# branches_v40.net
KiCad netlist of a schematic drawn in EAGLE
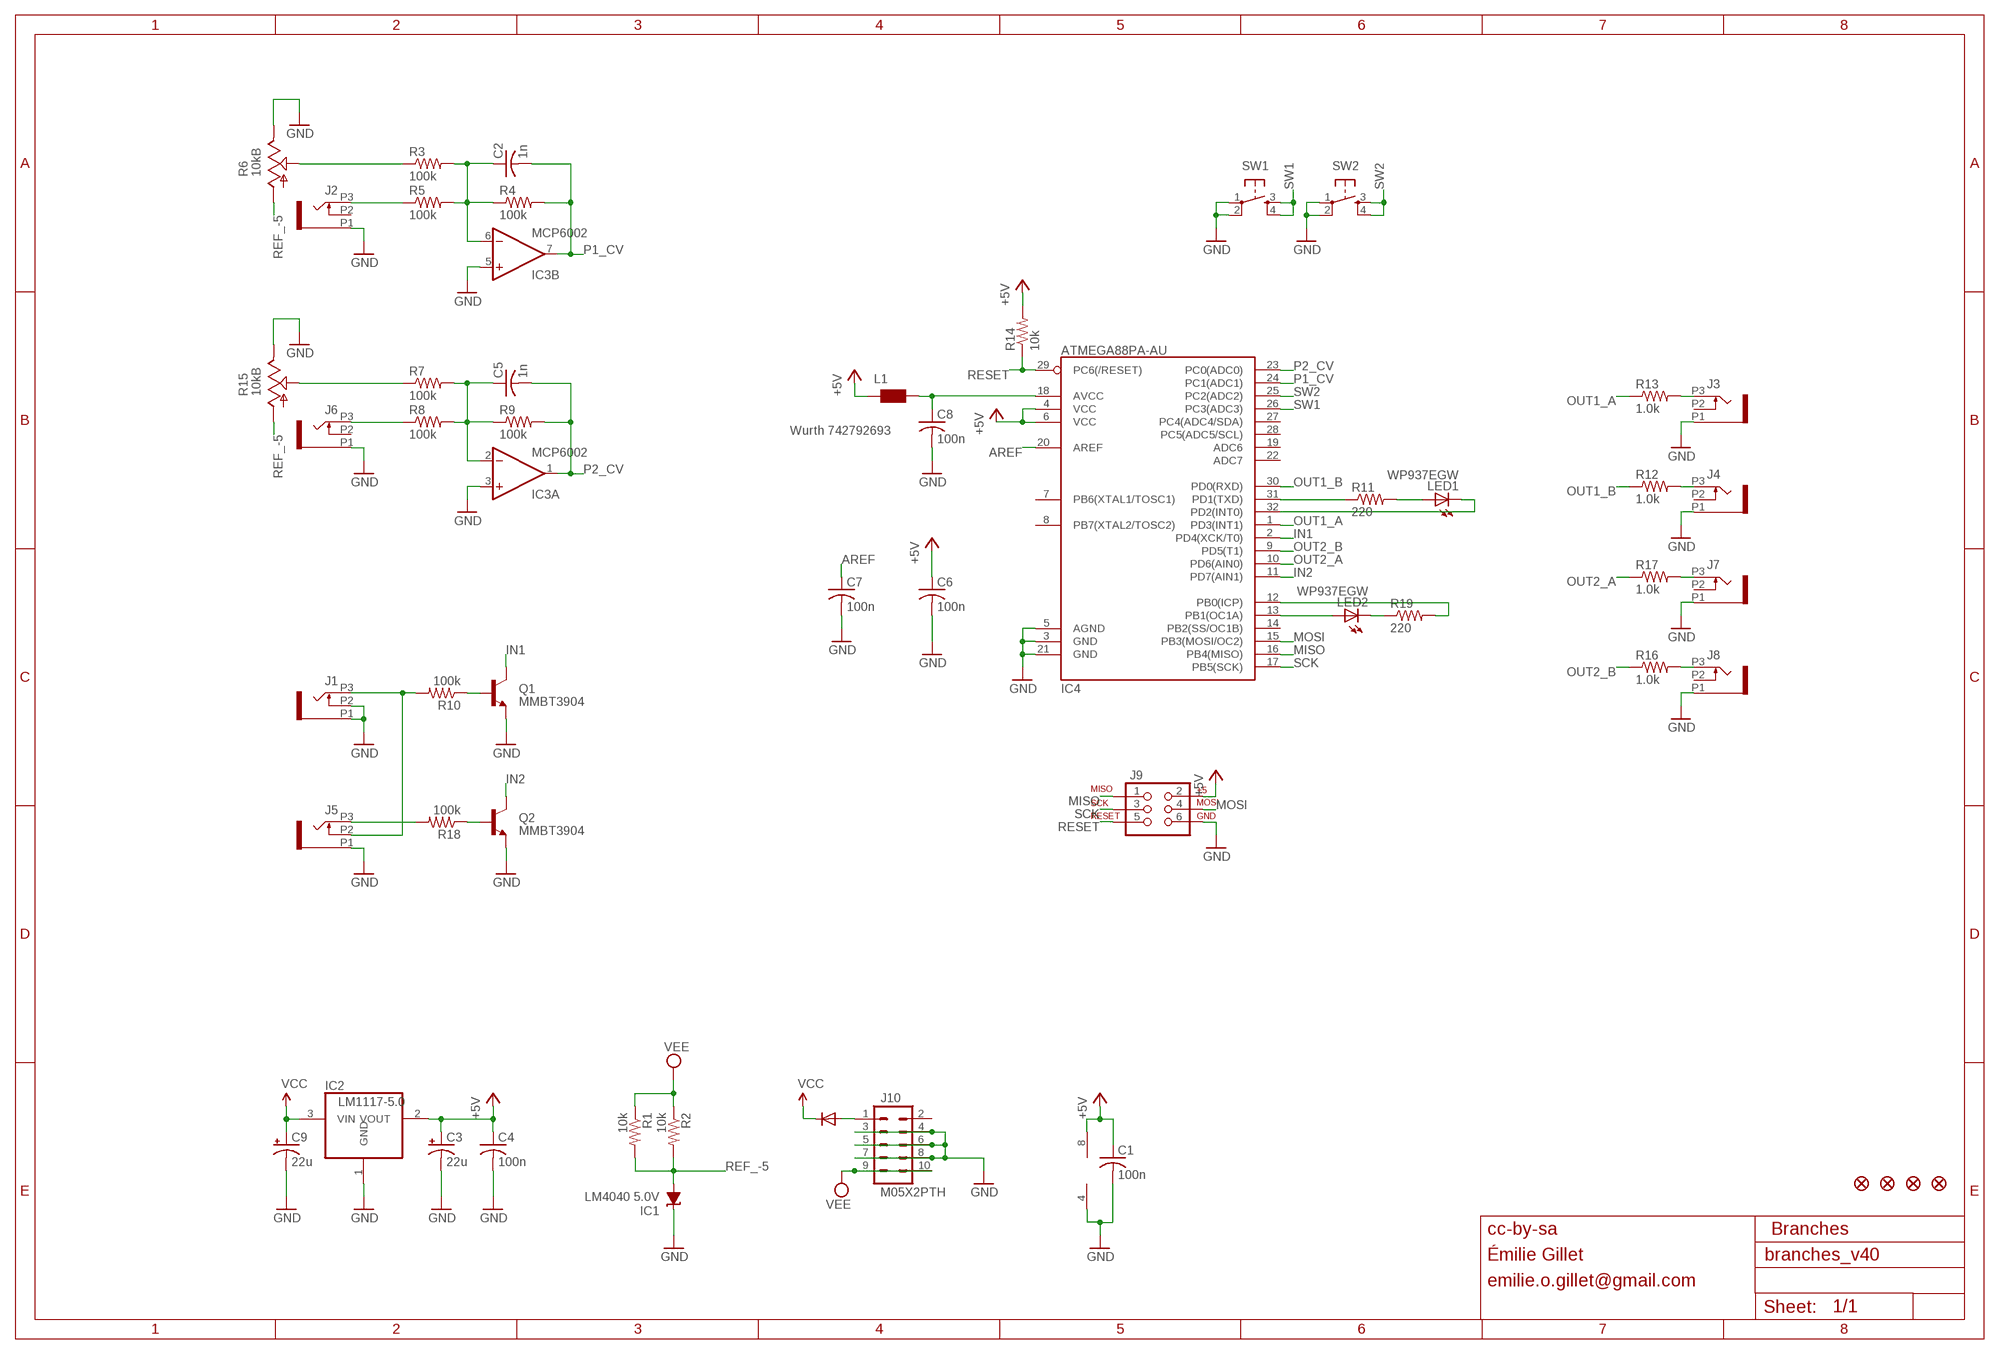
[diagram p0: schematic, sheet 1]

(export (version "E")
  (design (tool "Eeschema 10.0.6"))
  (components
    (comp (ref "C1")
      (value "100n")
      (footprint "eagle-import:C0603")
      (libsource (lib "eagle-import") (part "C-USC0603"))
    )
    (comp (ref "C2")
      (value "1n")
      (footprint "eagle-import:C0603")
      (libsource (lib "eagle-import") (part "C-USC0603"))
    )
    (comp (ref "C3")
      (value "22u")
      (footprint "eagle-import:PANASONIC_C")
      (libsource (lib "eagle-import") (part "CPOL-USC"))
    )
    (comp (ref "C4")
      (value "100n")
      (footprint "eagle-import:C0603")
      (libsource (lib "eagle-import") (part "C-USC0603"))
    )
    (comp (ref "C5")
      (value "1n")
      (footprint "eagle-import:C0603")
      (libsource (lib "eagle-import") (part "C-USC0603"))
    )
    (comp (ref "C6")
      (value "100n")
      (footprint "eagle-import:C0603")
      (libsource (lib "eagle-import") (part "C-USC0603"))
    )
    (comp (ref "C7")
      (value "100n")
      (footprint "eagle-import:C0603")
      (libsource (lib "eagle-import") (part "C-USC0603"))
    )
    (comp (ref "C8")
      (value "100n")
      (footprint "eagle-import:C0603")
      (libsource (lib "eagle-import") (part "C-USC0603"))
    )
    (comp (ref "C9")
      (value "22u")
      (footprint "eagle-import:PANASONIC_C")
      (libsource (lib "eagle-import") (part "CPOL-USC"))
    )
    (comp (ref "D1")
      (value "1N5819HW")
      (footprint "eagle-import:SOD123")
      (libsource (lib "eagle-import") (part "DIODE-SOD123"))
    )
    (comp (ref "F1")
      (value "FIDUCIAL1X2")
      (footprint "eagle-import:FIDUCIAL-1X2")
      (libsource (lib "eagle-import") (part "FIDUCIAL1X2"))
    )
    (comp (ref "F2")
      (value "FIDUCIAL1X2")
      (footprint "eagle-import:FIDUCIAL-1X2")
      (libsource (lib "eagle-import") (part "FIDUCIAL1X2"))
    )
    (comp (ref "F3")
      (value "FIDUCIAL1X2")
      (footprint "eagle-import:FIDUCIAL-1X2")
      (libsource (lib "eagle-import") (part "FIDUCIAL1X2"))
    )
    (comp (ref "F4")
      (value "FIDUCIAL1X2")
      (footprint "eagle-import:FIDUCIAL-1X2")
      (libsource (lib "eagle-import") (part "FIDUCIAL1X2"))
    )
    (comp (ref "IC1")
      (value "LM4040 5.0V")
      (footprint "eagle-import:DBZ_R-PDSO-G3")
      (libsource (lib "eagle-import") (part "LM4041DBZC12"))
    )
    (comp (ref "IC2")
      (value "LM1117-5.0")
      (footprint "eagle-import:SOT223")
      (libsource (lib "eagle-import") (part "REG1117"))
    )
    (comp (ref "IC3")
      (value "MCP6002")
      (footprint "eagle-import:SO08")
      (libsource (lib "eagle-import") (part "TL072D"))
    )
    (comp (ref "IC4")
      (value "ATMEGA88PA-AU")
      (footprint "eagle-import:TQFP32-08")
      (libsource (lib "eagle-import") (part "ATMEGA168"))
    )
    (comp (ref "J1")
      (value "PJ301_THONKICONN6")
      (footprint "eagle-import:WQP_PJ_301M6")
      (libsource (lib "eagle-import") (part "PJ301_THONKICONN6"))
    )
    (comp (ref "J2")
      (value "PJ301_THONKICONN6")
      (footprint "eagle-import:WQP_PJ_301M6")
      (libsource (lib "eagle-import") (part "PJ301_THONKICONN6"))
    )
    (comp (ref "J3")
      (value "PJ301_THONKICONN6")
      (footprint "eagle-import:WQP_PJ_301M6")
      (libsource (lib "eagle-import") (part "PJ301_THONKICONN6"))
    )
    (comp (ref "J4")
      (value "PJ301_THONKICONN6")
      (footprint "eagle-import:WQP_PJ_301M6")
      (libsource (lib "eagle-import") (part "PJ301_THONKICONN6"))
    )
    (comp (ref "J5")
      (value "PJ301_THONKICONN6")
      (footprint "eagle-import:WQP_PJ_301M6")
      (libsource (lib "eagle-import") (part "PJ301_THONKICONN6"))
    )
    (comp (ref "J6")
      (value "PJ301_THONKICONN6")
      (footprint "eagle-import:WQP_PJ_301M6")
      (libsource (lib "eagle-import") (part "PJ301_THONKICONN6"))
    )
    (comp (ref "J7")
      (value "PJ301_THONKICONN6")
      (footprint "eagle-import:WQP_PJ_301M6")
      (libsource (lib "eagle-import") (part "PJ301_THONKICONN6"))
    )
    (comp (ref "J8")
      (value "PJ301_THONKICONN6")
      (footprint "eagle-import:WQP_PJ_301M6")
      (libsource (lib "eagle-import") (part "PJ301_THONKICONN6"))
    )
    (comp (ref "J9")
      (value "AVR_SPI_PRG_6PTH")
      (footprint "eagle-import:2X3")
      (libsource (lib "eagle-import") (part "AVR_SPI_PRG_6PTH"))
    )
    (comp (ref "J10")
      (value "M05X2PTH")
      (footprint "eagle-import:AVR_ICSP")
      (libsource (lib "eagle-import") (part "M05X2PTH"))
    )
    (comp (ref "L1")
      (value "WE-CBF_0603")
      (footprint "eagle-import:0603")
      (libsource (lib "eagle-import") (part "WE-CBF_0603"))
    )
    (comp (ref "LED1")
      (value "WP937EGW")
      (footprint "eagle-import:LED3MM")
      (libsource (lib "eagle-import") (part "LED3MM"))
    )
    (comp (ref "LED2")
      (value "WP937EGW")
      (footprint "eagle-import:LED3MM")
      (libsource (lib "eagle-import") (part "LED3MM"))
    )
    (comp (ref "Q1")
      (value "MMBT3904")
      (footprint "eagle-import:SOT23-BEC")
      (libsource (lib "eagle-import") (part "-NPN-SOT23-BECMMBT3904LT1"))
    )
    (comp (ref "Q2")
      (value "MMBT3904")
      (footprint "eagle-import:SOT23-BEC")
      (libsource (lib "eagle-import") (part "-NPN-SOT23-BECMMBT3904LT1"))
    )
    (comp (ref "R1")
      (value "10k")
      (footprint "eagle-import:R0603")
      (libsource (lib "eagle-import") (part "resistor_R-US_R0603"))
    )
    (comp (ref "R2")
      (value "10k")
      (footprint "eagle-import:R0603")
      (libsource (lib "eagle-import") (part "resistor_R-US_R0603"))
    )
    (comp (ref "R3")
      (value "100k")
      (footprint "eagle-import:R0603")
      (libsource (lib "eagle-import") (part "R-US_R0603"))
    )
    (comp (ref "R4")
      (value "100k")
      (footprint "eagle-import:R0603")
      (libsource (lib "eagle-import") (part "R-US_R0603"))
    )
    (comp (ref "R5")
      (value "100k")
      (footprint "eagle-import:R0603")
      (libsource (lib "eagle-import") (part "R-US_R0603"))
    )
    (comp (ref "R6")
      (value "10kB")
      (footprint "eagle-import:ALPS_POT_VERTICAL_PS")
      (libsource (lib "eagle-import") (part "POT_USVERTICAL_PS"))
    )
    (comp (ref "R7")
      (value "100k")
      (footprint "eagle-import:R0603")
      (libsource (lib "eagle-import") (part "R-US_R0603"))
    )
    (comp (ref "R8")
      (value "100k")
      (footprint "eagle-import:R0603")
      (libsource (lib "eagle-import") (part "R-US_R0603"))
    )
    (comp (ref "R9")
      (value "100k")
      (footprint "eagle-import:R0603")
      (libsource (lib "eagle-import") (part "R-US_R0603"))
    )
    (comp (ref "R10")
      (value "100k")
      (footprint "eagle-import:R0603")
      (libsource (lib "eagle-import") (part "R-US_R0603"))
    )
    (comp (ref "R11")
      (value "220")
      (footprint "eagle-import:R0603")
      (libsource (lib "eagle-import") (part "R-US_R0603"))
    )
    (comp (ref "R12")
      (value "1.0k")
      (footprint "eagle-import:R0603")
      (libsource (lib "eagle-import") (part "R-US_R0603"))
    )
    (comp (ref "R13")
      (value "1.0k")
      (footprint "eagle-import:R0603")
      (libsource (lib "eagle-import") (part "R-US_R0603"))
    )
    (comp (ref "R14")
      (value "10k")
      (footprint "eagle-import:R0603")
      (libsource (lib "eagle-import") (part "R-US_R0603"))
    )
    (comp (ref "R15")
      (value "10kB")
      (footprint "eagle-import:ALPS_POT_VERTICAL_PS")
      (libsource (lib "eagle-import") (part "POT_USVERTICAL_PS"))
    )
    (comp (ref "R16")
      (value "1.0k")
      (footprint "eagle-import:R0603")
      (libsource (lib "eagle-import") (part "R-US_R0603"))
    )
    (comp (ref "R17")
      (value "1.0k")
      (footprint "eagle-import:R0603")
      (libsource (lib "eagle-import") (part "R-US_R0603"))
    )
    (comp (ref "R18")
      (value "100k")
      (footprint "eagle-import:R0603")
      (libsource (lib "eagle-import") (part "R-US_R0603"))
    )
    (comp (ref "R19")
      (value "220")
      (footprint "eagle-import:R0603")
      (libsource (lib "eagle-import") (part "R-US_R0603"))
    )
    (comp (ref "SW1")
      (value "TAC_SWITCHPTH")
      (footprint "eagle-import:TACTILE-PTH")
      (libsource (lib "eagle-import") (part "TAC_SWITCHPTH"))
    )
    (comp (ref "SW2")
      (value "TAC_SWITCHPTH")
      (footprint "eagle-import:TACTILE-PTH")
      (libsource (lib "eagle-import") (part "TAC_SWITCHPTH"))
    )
  )
  (nets
    (net (code "1") (name "+5V") (class "Default")
      (node (ref "C1") (pin "1") (pinfunction "1_1") (pintype "passive"))
      (node (ref "C3") (pin "+") (pinfunction "+_+") (pintype "passive"))
      (node (ref "C4") (pin "1") (pinfunction "1_1") (pintype "passive"))
      (node (ref "C6") (pin "1") (pinfunction "1_1") (pintype "passive"))
      (node (ref "IC2") (pin "2") (pinfunction "VOUT_2") (pintype "output"))
      (node (ref "IC3") (pin "8") (pinfunction "V+_8") (pintype "power_in"))
      (node (ref "IC4") (pin "4") (pinfunction "VCC_4") (pintype "bidirectional"))
      (node (ref "IC4") (pin "6") (pinfunction "VCC_6") (pintype "bidirectional"))
      (node (ref "J9") (pin "2") (pinfunction "2_2") (pintype "passive"))
      (node (ref "L1") (pin "1") (pinfunction "1_1") (pintype "passive"))
      (node (ref "R14") (pin "2") (pinfunction "2_2") (pintype "passive"))
    )
    (net (code "2") (name "/AREF") (class "Default")
      (node (ref "C7") (pin "1") (pinfunction "1_1") (pintype "passive"))
      (node (ref "IC4") (pin "20") (pinfunction "AREF_20") (pintype "bidirectional"))
    )
    (net (code "3") (name "/IN1") (class "Default")
      (node (ref "IC4") (pin "2") (pinfunction "PD4(XCK/T0)_2") (pintype "bidirectional"))
      (node (ref "Q1") (pin "C") (pinfunction "C_C") (pintype "passive"))
    )
    (net (code "4") (name "/IN2") (class "Default")
      (node (ref "IC4") (pin "11") (pinfunction "PD7(AIN1)_11") (pintype "bidirectional"))
      (node (ref "Q2") (pin "C") (pinfunction "C_C") (pintype "passive"))
    )
    (net (code "5") (name "/MISO") (class "Default")
      (node (ref "IC4") (pin "16") (pinfunction "PB4(MISO)_16") (pintype "bidirectional"))
      (node (ref "J9") (pin "1") (pinfunction "1_1") (pintype "passive"))
    )
    (net (code "6") (name "/MOSI") (class "Default")
      (node (ref "IC4") (pin "15") (pinfunction "PB3(MOSI/OC2)_15") (pintype "bidirectional"))
      (node (ref "J9") (pin "4") (pinfunction "4_4") (pintype "passive"))
    )
    (net (code "7") (name "/OUT1_A") (class "Default")
      (node (ref "IC4") (pin "1") (pinfunction "PD3(INT1)_1") (pintype "bidirectional"))
      (node (ref "R13") (pin "1") (pinfunction "1_1") (pintype "passive"))
    )
    (net (code "8") (name "/OUT1_B") (class "Default")
      (node (ref "IC4") (pin "30") (pinfunction "PD0(RXD)_30") (pintype "bidirectional"))
      (node (ref "R12") (pin "1") (pinfunction "1_1") (pintype "passive"))
    )
    (net (code "9") (name "/OUT2_A") (class "Default")
      (node (ref "IC4") (pin "10") (pinfunction "PD6(AIN0)_10") (pintype "bidirectional"))
      (node (ref "R17") (pin "1") (pinfunction "1_1") (pintype "passive"))
    )
    (net (code "10") (name "/OUT2_B") (class "Default")
      (node (ref "IC4") (pin "9") (pinfunction "PD5(T1)_9") (pintype "bidirectional"))
      (node (ref "R16") (pin "1") (pinfunction "1_1") (pintype "passive"))
    )
    (net (code "11") (name "/P1_CV") (class "Default")
      (node (ref "C2") (pin "2") (pinfunction "2_2") (pintype "passive"))
      (node (ref "IC3") (pin "7") (pinfunction "OUT_7") (pintype "output"))
      (node (ref "IC4") (pin "24") (pinfunction "PC1(ADC1)_24") (pintype "bidirectional"))
      (node (ref "R4") (pin "2") (pinfunction "2_2") (pintype "passive"))
    )
    (net (code "12") (name "/P2_CV") (class "Default")
      (node (ref "C5") (pin "2") (pinfunction "2_2") (pintype "passive"))
      (node (ref "IC3") (pin "1") (pinfunction "OUT_1") (pintype "output"))
      (node (ref "IC4") (pin "23") (pinfunction "PC0(ADC0)_23") (pintype "bidirectional"))
      (node (ref "R9") (pin "2") (pinfunction "2_2") (pintype "passive"))
    )
    (net (code "13") (name "/REF_-5") (class "Default")
      (node (ref "IC1") (pin "2") (pinfunction "A_2") (pintype "passive"))
      (node (ref "R1") (pin "2") (pinfunction "2_2") (pintype "passive"))
      (node (ref "R15") (pin "P$3") (pinfunction "A_P$3") (pintype "passive"))
      (node (ref "R2") (pin "2") (pinfunction "2_2") (pintype "passive"))
      (node (ref "R6") (pin "P$3") (pinfunction "A_P$3") (pintype "passive"))
    )
    (net (code "14") (name "/RESET") (class "Default")
      (node (ref "IC4") (pin "29") (pinfunction "PC6(/RESET)_29") (pintype "bidirectional"))
      (node (ref "J9") (pin "5") (pinfunction "5_5") (pintype "passive"))
      (node (ref "R14") (pin "1") (pinfunction "1_1") (pintype "passive"))
    )
    (net (code "15") (name "/SCK") (class "Default")
      (node (ref "IC4") (pin "17") (pinfunction "PB5(SCK)_17") (pintype "bidirectional"))
      (node (ref "J9") (pin "3") (pinfunction "3_3") (pintype "passive"))
    )
    (net (code "16") (name "/SW1") (class "Default")
      (node (ref "IC4") (pin "26") (pinfunction "PC3(ADC3)_26") (pintype "bidirectional"))
      (node (ref "SW1") (pin "3") (pinfunction "3_3") (pintype "passive"))
      (node (ref "SW1") (pin "4") (pinfunction "4_4") (pintype "passive"))
    )
    (net (code "17") (name "/SW2") (class "Default")
      (node (ref "IC4") (pin "25") (pinfunction "PC2(ADC2)_25") (pintype "bidirectional"))
      (node (ref "SW2") (pin "3") (pinfunction "3_3") (pintype "passive"))
      (node (ref "SW2") (pin "4") (pinfunction "4_4") (pintype "passive"))
    )
    (net (code "18") (name "GND") (class "Default")
      (node (ref "C1") (pin "2") (pinfunction "2_2") (pintype "passive"))
      (node (ref "C3") (pin "-") (pinfunction "-_-") (pintype "passive"))
      (node (ref "C4") (pin "2") (pinfunction "2_2") (pintype "passive"))
      (node (ref "C6") (pin "2") (pinfunction "2_2") (pintype "passive"))
      (node (ref "C7") (pin "2") (pinfunction "2_2") (pintype "passive"))
      (node (ref "C8") (pin "2") (pinfunction "2_2") (pintype "passive"))
      (node (ref "C9") (pin "-") (pinfunction "-_-") (pintype "passive"))
      (node (ref "IC1") (pin "1") (pinfunction "C_1") (pintype "passive"))
      (node (ref "IC2") (pin "1") (pinfunction "GND_1") (pintype "power_in"))
      (node (ref "IC3") (pin "3") (pinfunction "+IN_3") (pintype "input"))
      (node (ref "IC3") (pin "4") (pinfunction "V-_4") (pintype "power_in"))
      (node (ref "IC3") (pin "5") (pinfunction "+IN_5") (pintype "input"))
      (node (ref "IC4") (pin "21") (pinfunction "GND_21") (pintype "bidirectional"))
      (node (ref "IC4") (pin "3") (pinfunction "GND_3") (pintype "bidirectional"))
      (node (ref "IC4") (pin "5") (pinfunction "AGND_5") (pintype "bidirectional"))
      (node (ref "J1") (pin "P1") (pinfunction "1_P1") (pintype "passive"))
      (node (ref "J1") (pin "P2") (pinfunction "2_P2") (pintype "passive"))
      (node (ref "J10") (pin "3") (pinfunction "3_3") (pintype "passive"))
      (node (ref "J10") (pin "4") (pinfunction "4_4") (pintype "passive"))
      (node (ref "J10") (pin "5") (pinfunction "5_5") (pintype "passive"))
      (node (ref "J10") (pin "6") (pinfunction "6_6") (pintype "passive"))
      (node (ref "J10") (pin "7") (pinfunction "7_7") (pintype "passive"))
      (node (ref "J10") (pin "8") (pinfunction "8_8") (pintype "passive"))
      (node (ref "J2") (pin "P1") (pinfunction "1_P1") (pintype "passive"))
      (node (ref "J3") (pin "P1") (pinfunction "1_P1") (pintype "passive"))
      (node (ref "J4") (pin "P1") (pinfunction "1_P1") (pintype "passive"))
      (node (ref "J5") (pin "P1") (pinfunction "1_P1") (pintype "passive"))
      (node (ref "J6") (pin "P1") (pinfunction "1_P1") (pintype "passive"))
      (node (ref "J7") (pin "P1") (pinfunction "1_P1") (pintype "passive"))
      (node (ref "J8") (pin "P1") (pinfunction "1_P1") (pintype "passive"))
      (node (ref "J9") (pin "6") (pinfunction "6_6") (pintype "passive"))
      (node (ref "Q1") (pin "E") (pinfunction "E_E") (pintype "passive"))
      (node (ref "Q2") (pin "E") (pinfunction "E_E") (pintype "passive"))
      (node (ref "R15") (pin "P$1") (pinfunction "E_P$1") (pintype "passive"))
      (node (ref "R6") (pin "P$1") (pinfunction "E_P$1") (pintype "passive"))
      (node (ref "SW1") (pin "1") (pinfunction "1_1") (pintype "passive"))
      (node (ref "SW1") (pin "2") (pinfunction "2_2") (pintype "passive"))
      (node (ref "SW2") (pin "1") (pinfunction "1_1") (pintype "passive"))
      (node (ref "SW2") (pin "2") (pinfunction "2_2") (pintype "passive"))
    )
    (net (code "19") (name "Net-(D1-PadA)") (class "Default")
      (node (ref "D1") (pin "A") (pinfunction "A_A") (pintype "passive"))
      (node (ref "J10") (pin "1") (pinfunction "1_1") (pintype "passive"))
    )
    (net (code "20") (name "Net-(IC3A--IN)") (class "Default")
      (node (ref "C5") (pin "1") (pinfunction "1_1") (pintype "passive"))
      (node (ref "IC3") (pin "2") (pinfunction "-IN_2") (pintype "input"))
      (node (ref "R7") (pin "2") (pinfunction "2_2") (pintype "passive"))
      (node (ref "R8") (pin "2") (pinfunction "2_2") (pintype "passive"))
      (node (ref "R9") (pin "1") (pinfunction "1_1") (pintype "passive"))
    )
    (net (code "21") (name "Net-(IC3B--IN)") (class "Default")
      (node (ref "C2") (pin "1") (pinfunction "1_1") (pintype "passive"))
      (node (ref "IC3") (pin "6") (pinfunction "-IN_6") (pintype "input"))
      (node (ref "R3") (pin "2") (pinfunction "2_2") (pintype "passive"))
      (node (ref "R4") (pin "1") (pinfunction "1_1") (pintype "passive"))
      (node (ref "R5") (pin "2") (pinfunction "2_2") (pintype "passive"))
    )
    (net (code "22") (name "Net-(IC4-AVCC)") (class "Default")
      (node (ref "C8") (pin "1") (pinfunction "1_1") (pintype "passive"))
      (node (ref "IC4") (pin "18") (pinfunction "AVCC_18") (pintype "bidirectional"))
      (node (ref "L1") (pin "2") (pinfunction "2_2") (pintype "passive"))
    )
    (net (code "23") (name "Net-(IC4-PB0(ICP))") (class "Default")
      (node (ref "IC4") (pin "12") (pinfunction "PB0(ICP)_12") (pintype "bidirectional"))
      (node (ref "R19") (pin "2") (pinfunction "2_2") (pintype "passive"))
    )
    (net (code "24") (name "Net-(IC4-PB1(OC1A))") (class "Default")
      (node (ref "IC4") (pin "13") (pinfunction "PB1(OC1A)_13") (pintype "bidirectional"))
      (node (ref "LED2") (pin "A") (pinfunction "A_A") (pintype "passive"))
    )
    (net (code "25") (name "Net-(IC4-PD1(TXD))") (class "Default")
      (node (ref "IC4") (pin "31") (pinfunction "PD1(TXD)_31") (pintype "bidirectional"))
      (node (ref "R11") (pin "1") (pinfunction "1_1") (pintype "passive"))
    )
    (net (code "26") (name "Net-(IC4-PD2(INT0))") (class "Default")
      (node (ref "IC4") (pin "32") (pinfunction "PD2(INT0)_32") (pintype "bidirectional"))
      (node (ref "LED1") (pin "K") (pinfunction "C_K") (pintype "passive"))
    )
    (net (code "27") (name "Net-(J1-3)") (class "Default")
      (node (ref "J1") (pin "P3") (pinfunction "3_P3") (pintype "passive"))
      (node (ref "J5") (pin "P2") (pinfunction "2_P2") (pintype "passive"))
      (node (ref "R10") (pin "2") (pinfunction "2_2") (pintype "passive"))
    )
    (net (code "28") (name "Net-(J2-3)") (class "Default")
      (node (ref "J2") (pin "P3") (pinfunction "3_P3") (pintype "passive"))
      (node (ref "R5") (pin "1") (pinfunction "1_1") (pintype "passive"))
    )
    (net (code "29") (name "Net-(J3-3)") (class "Default")
      (node (ref "J3") (pin "P3") (pinfunction "3_P3") (pintype "passive"))
      (node (ref "R13") (pin "2") (pinfunction "2_2") (pintype "passive"))
    )
    (net (code "30") (name "Net-(J4-3)") (class "Default")
      (node (ref "J4") (pin "P3") (pinfunction "3_P3") (pintype "passive"))
      (node (ref "R12") (pin "2") (pinfunction "2_2") (pintype "passive"))
    )
    (net (code "31") (name "Net-(J5-3)") (class "Default")
      (node (ref "J5") (pin "P3") (pinfunction "3_P3") (pintype "passive"))
      (node (ref "R18") (pin "2") (pinfunction "2_2") (pintype "passive"))
    )
    (net (code "32") (name "Net-(J6-3)") (class "Default")
      (node (ref "J6") (pin "P3") (pinfunction "3_P3") (pintype "passive"))
      (node (ref "R8") (pin "1") (pinfunction "1_1") (pintype "passive"))
    )
    (net (code "33") (name "Net-(J7-3)") (class "Default")
      (node (ref "J7") (pin "P3") (pinfunction "3_P3") (pintype "passive"))
      (node (ref "R17") (pin "2") (pinfunction "2_2") (pintype "passive"))
    )
    (net (code "34") (name "Net-(J8-3)") (class "Default")
      (node (ref "J8") (pin "P3") (pinfunction "3_P3") (pintype "passive"))
      (node (ref "R16") (pin "2") (pinfunction "2_2") (pintype "passive"))
    )
    (net (code "35") (name "Net-(LED1-PadA)") (class "Default")
      (node (ref "LED1") (pin "A") (pinfunction "A_A") (pintype "passive"))
      (node (ref "R11") (pin "2") (pinfunction "2_2") (pintype "passive"))
    )
    (net (code "36") (name "Net-(LED2-C)") (class "Default")
      (node (ref "LED2") (pin "K") (pinfunction "C_K") (pintype "passive"))
      (node (ref "R19") (pin "1") (pinfunction "1_1") (pintype "passive"))
    )
    (net (code "37") (name "Net-(Q1-PadB)") (class "Default")
      (node (ref "Q1") (pin "B") (pinfunction "B_B") (pintype "passive"))
      (node (ref "R10") (pin "1") (pinfunction "1_1") (pintype "passive"))
    )
    (net (code "38") (name "Net-(Q2-PadB)") (class "Default")
      (node (ref "Q2") (pin "B") (pinfunction "B_B") (pintype "passive"))
      (node (ref "R18") (pin "1") (pinfunction "1_1") (pintype "passive"))
    )
    (net (code "39") (name "Net-(R6-S)") (class "Default")
      (node (ref "R3") (pin "1") (pinfunction "1_1") (pintype "passive"))
      (node (ref "R6") (pin "P$2") (pinfunction "S_P$2") (pintype "passive"))
    )
    (net (code "40") (name "Net-(R15-S)") (class "Default")
      (node (ref "R15") (pin "P$2") (pinfunction "S_P$2") (pintype "passive"))
      (node (ref "R7") (pin "1") (pinfunction "1_1") (pintype "passive"))
    )
    (net (code "41") (name "VCC") (class "Default")
      (node (ref "C9") (pin "+") (pinfunction "+_+") (pintype "passive"))
      (node (ref "D1") (pin "C") (pinfunction "C_C") (pintype "passive"))
      (node (ref "IC2") (pin "3") (pinfunction "VIN_3") (pintype "input"))
    )
    (net (code "42") (name "VEE") (class "Default")
      (node (ref "J10") (pin "10") (pinfunction "10_10") (pintype "passive"))
      (node (ref "J10") (pin "9") (pinfunction "9_9") (pintype "passive"))
      (node (ref "R1") (pin "1") (pinfunction "1_1") (pintype "passive"))
      (node (ref "R2") (pin "1") (pinfunction "1_1") (pintype "passive"))
    )
    (net (code "43") (name "unconnected-(IC4-ADC6-Pad19)") (class "Default")
      (node (ref "IC4") (pin "19") (pinfunction "ADC6_19") (pintype "bidirectional"))
    )
    (net (code "44") (name "unconnected-(IC4-ADC7-Pad22)") (class "Default")
      (node (ref "IC4") (pin "22") (pinfunction "ADC7_22") (pintype "bidirectional"))
    )
    (net (code "45") (name "unconnected-(IC4-PB2(SS{slash}OC1B)-Pad14)") (class "Default")
      (node (ref "IC4") (pin "14") (pinfunction "PB2(SS/OC1B)_14") (pintype "bidirectional"))
    )
    (net (code "46") (name "unconnected-(IC4-PB6(XTAL1{slash}TOSC1)-Pad7)") (class "Default")
      (node (ref "IC4") (pin "7") (pinfunction "PB6(XTAL1/TOSC1)_7") (pintype "bidirectional"))
    )
    (net (code "47") (name "unconnected-(IC4-PB7(XTAL2{slash}TOSC2)-Pad8)") (class "Default")
      (node (ref "IC4") (pin "8") (pinfunction "PB7(XTAL2/TOSC2)_8") (pintype "bidirectional"))
    )
    (net (code "48") (name "unconnected-(IC4-PC4(ADC4{slash}SDA)-Pad27)") (class "Default")
      (node (ref "IC4") (pin "27") (pinfunction "PC4(ADC4/SDA)_27") (pintype "bidirectional"))
    )
    (net (code "49") (name "unconnected-(IC4-PC5(ADC5{slash}SCL)-Pad28)") (class "Default")
      (node (ref "IC4") (pin "28") (pinfunction "PC5(ADC5/SCL)_28") (pintype "bidirectional"))
    )
    (net (code "50") (name "unconnected-(J2-2-PadP2)") (class "Default")
      (node (ref "J2") (pin "P2") (pinfunction "2_P2") (pintype "passive"))
    )
    (net (code "51") (name "unconnected-(J3-2-PadP2)") (class "Default")
      (node (ref "J3") (pin "P2") (pinfunction "2_P2") (pintype "passive"))
    )
    (net (code "52") (name "unconnected-(J4-2-PadP2)") (class "Default")
      (node (ref "J4") (pin "P2") (pinfunction "2_P2") (pintype "passive"))
    )
    (net (code "53") (name "unconnected-(J6-2-PadP2)") (class "Default")
      (node (ref "J6") (pin "P2") (pinfunction "2_P2") (pintype "passive"))
    )
    (net (code "54") (name "unconnected-(J7-2-PadP2)") (class "Default")
      (node (ref "J7") (pin "P2") (pinfunction "2_P2") (pintype "passive"))
    )
    (net (code "55") (name "unconnected-(J8-2-PadP2)") (class "Default")
      (node (ref "J8") (pin "P2") (pinfunction "2_P2") (pintype "passive"))
    )
    (net (code "56") (name "unconnected-(J10-Pad2)") (class "Default")
      (node (ref "J10") (pin "2") (pinfunction "2_2") (pintype "passive"))
    )
  )
)
